# TK530_Kraftbakplan.net
KiCad netlist of a schematic drawn in Altium Designer
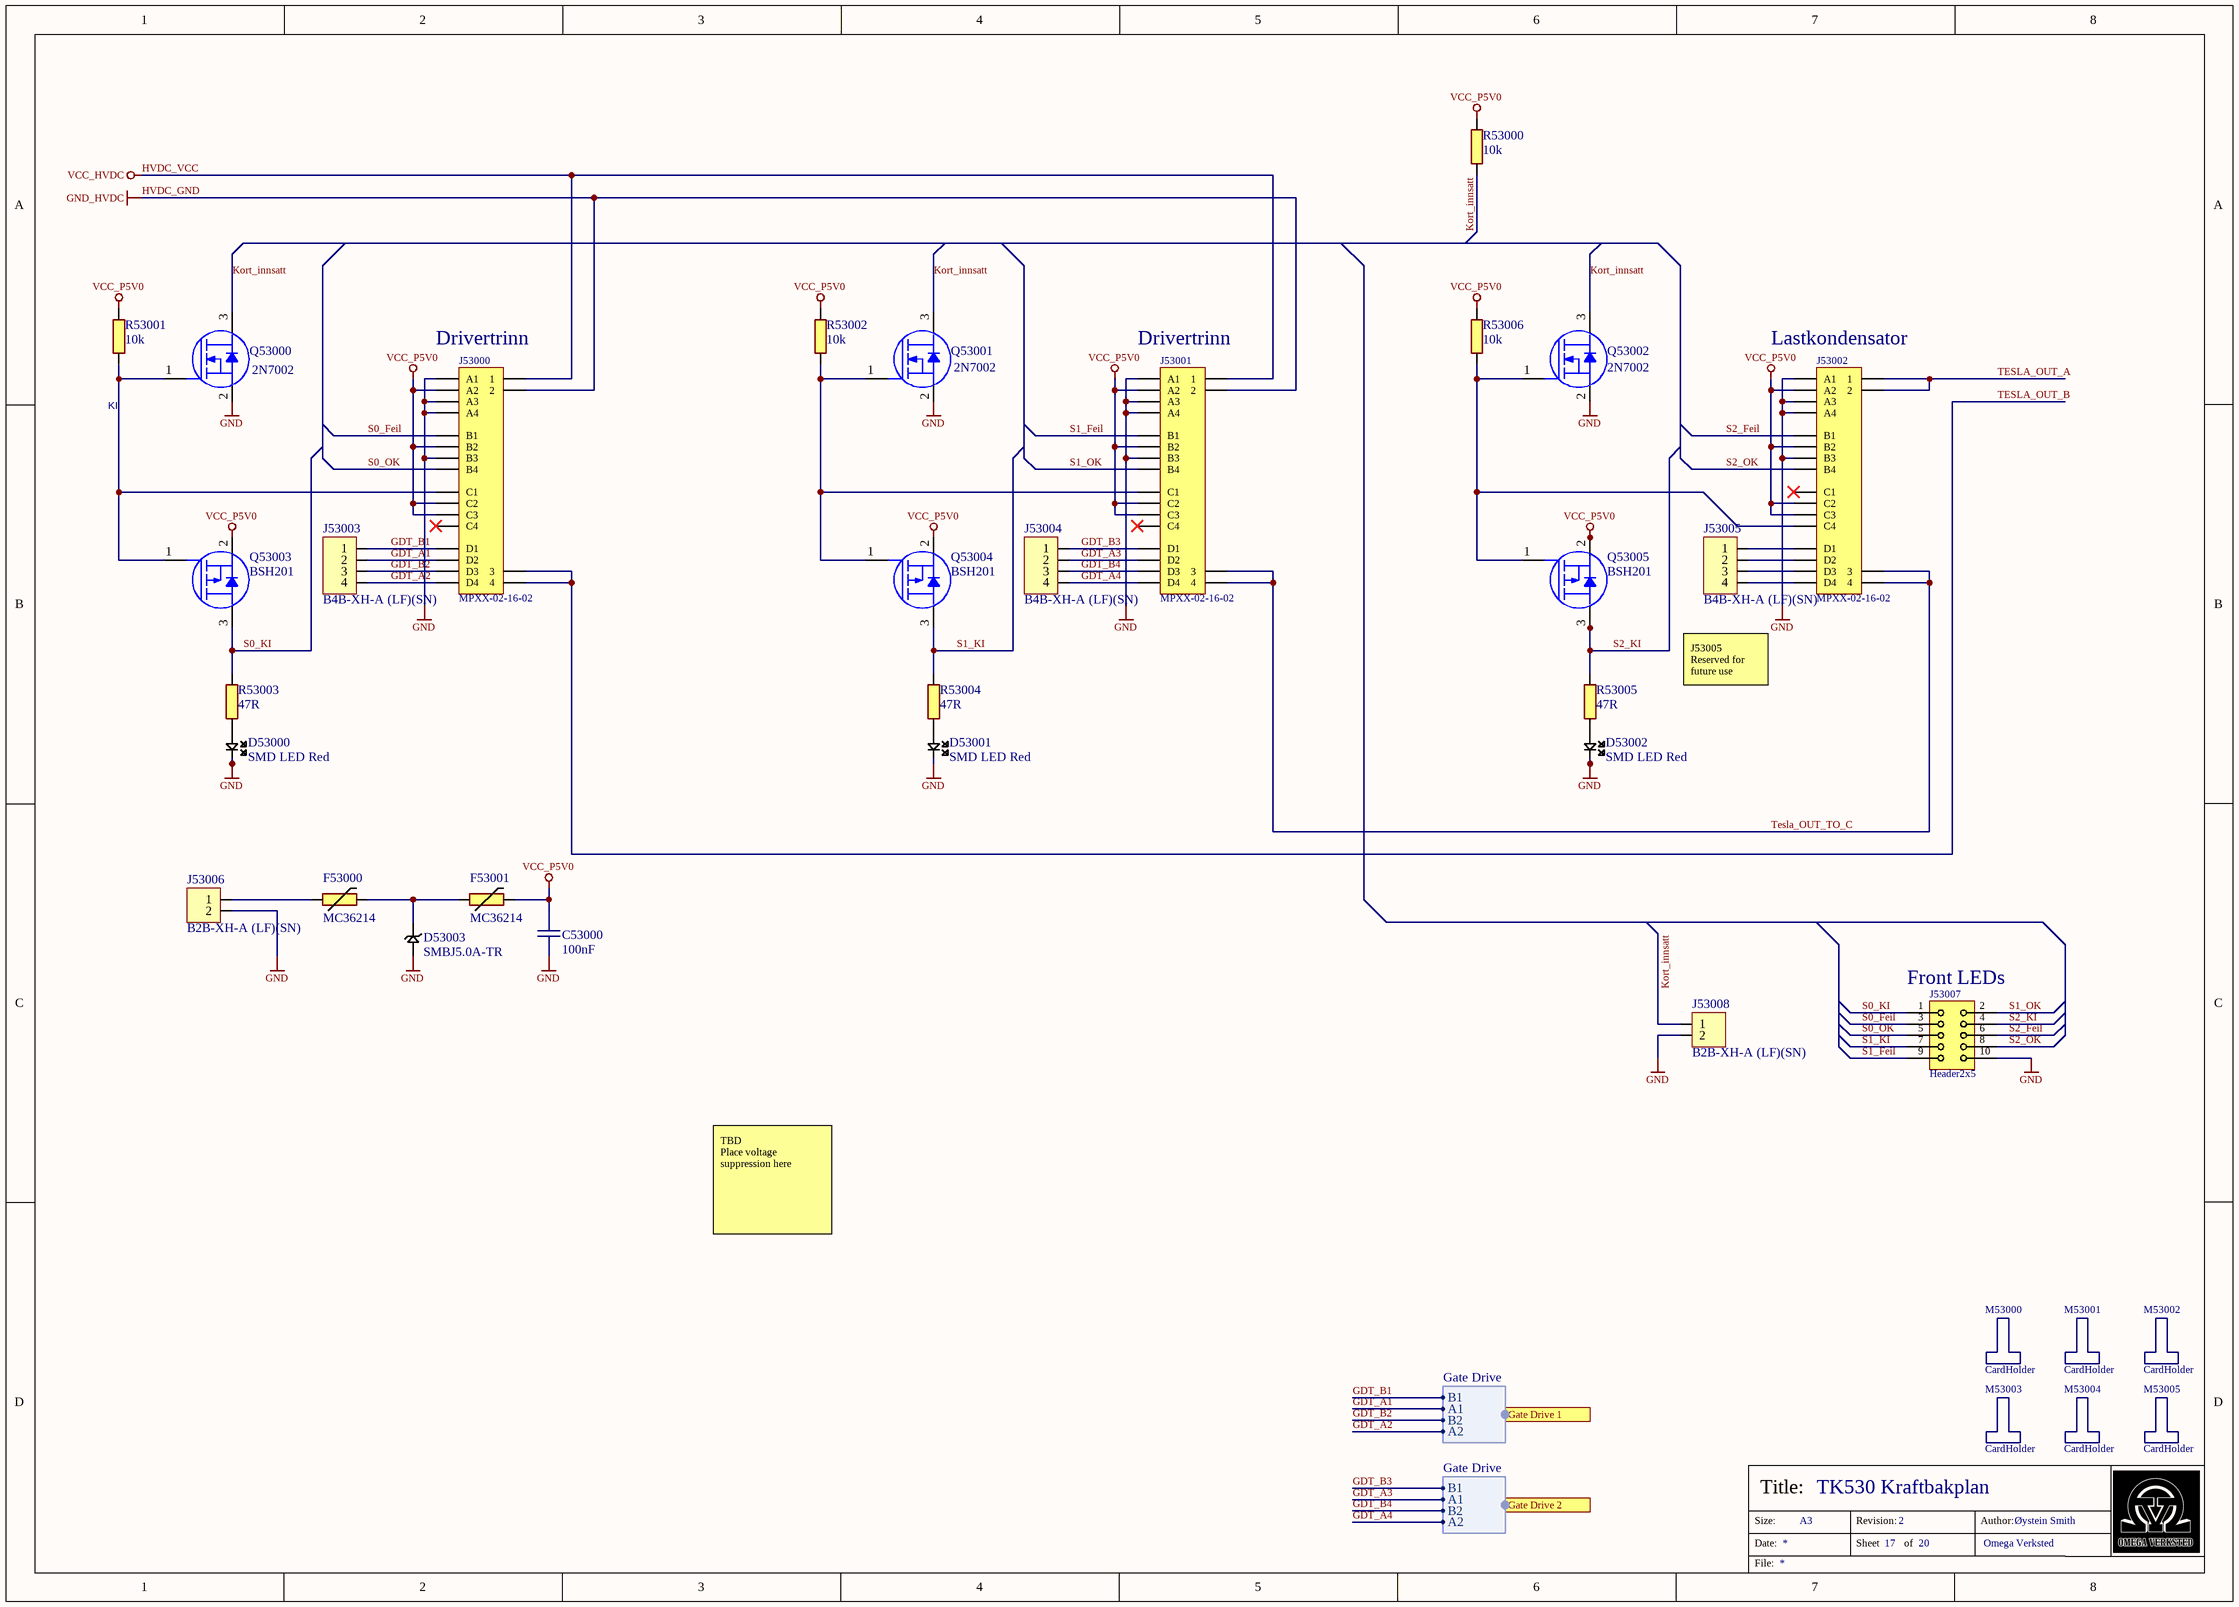
[diagram p0: TK530_Kraftbakplan.SchDoc]

(export (version "E")
  (design (tool "Eeschema 10.0.6"))
  (components
    (comp (ref "C53000")
      (value "100nF")
      (footprint "CAPC0603(1608)55_N")
      (description "X7R 50V 5%")
      (libsource (lib "OVLib_64") (part "CAP"))
    )
    (comp (ref "D53000")
      (value "SMD LED Red")
      (footprint "I_LEDC0603(1608)_N")
      (description "SMD")
      (libsource (lib "OVLib_64") (part "LED"))
    )
    (comp (ref "D53001")
      (value "SMD LED Red")
      (footprint "I_LEDC0603(1608)_N")
      (description "SMD")
      (libsource (lib "OVLib_64") (part "LED"))
    )
    (comp (ref "D53002")
      (value "SMD LED Red")
      (footprint "I_LEDC0603(1608)_N")
      (description "SMD")
      (libsource (lib "OVLib_64") (part "LED"))
    )
    (comp (ref "D53003")
      (value "SMBJ5.0A-TR")
      (footprint "SODFL535X245-2N")
      (description "Transient Voltage Suppressor, TVS, Transil SMBJ Series, Unidirectional, 5 V, SMD, 2, 6.4 V")
      (libsource (lib "OVLib_64") (part "TVSDiode"))
    )
    (comp (ref "F53000")
      (value "MC36214")
      (footprint "RESC0805(2012)_N")
      (description "FUSE, PTC RESET, SMD, 16V, 500MA")
      (libsource (lib "OVLib_64") (part "PTC"))
    )
    (comp (ref "F53001")
      (value "MC36214")
      (footprint "RESC0805(2012)_N")
      (description "FUSE, PTC RESET, SMD, 16V, 500MA")
      (libsource (lib "OVLib_64") (part "PTC"))
    )
    (comp (ref "J53000")
      (value "MPXX-02-16-02")
      (footprint "MPSC-02-16-02-7.70-03-L-V-LC")
      (description "SAMTEC Connector")
      (libsource (lib "OVLib_64") (part "MPXX-02-16-02"))
    )
    (comp (ref "J53001")
      (value "MPXX-02-16-02")
      (footprint "MPSC-02-16-02-7.70-03-L-V-LC")
      (description "SAMTEC Connector")
      (libsource (lib "OVLib_64") (part "MPXX-02-16-02"))
    )
    (comp (ref "J53002")
      (value "MPXX-02-16-02")
      (footprint "MPSC-02-16-02-7.70-03-L-V-LC")
      (description "SAMTEC Connector")
      (libsource (lib "OVLib_64") (part "MPXX-02-16-02"))
    )
    (comp (ref "J53003")
      (value "B4B-XH-A (LF)(SN)")
      (footprint "JST_4P")
      (description "JST 4pin (pris pr. stk.)")
      (libsource (lib "OVLib_64") (part "4PConnector"))
    )
    (comp (ref "J53004")
      (value "B4B-XH-A (LF)(SN)")
      (footprint "JST_4P")
      (description "JST 4pin (pris pr. stk.)")
      (libsource (lib "OVLib_64") (part "4PConnector"))
    )
    (comp (ref "J53005")
      (value "B4B-XH-A (LF)(SN)")
      (footprint "JST_4P")
      (description "JST 4pin (pris pr. stk.)")
      (libsource (lib "OVLib_64") (part "4PConnector"))
    )
    (comp (ref "J53006")
      (value "B2B-XH-A (LF)(SN)")
      (footprint "JST_2P")
      (description "JST 2pin (pris pr. stk.)")
      (libsource (lib "OVLib_64") (part "2PConnector"))
    )
    (comp (ref "J53007")
      (value "Header2x5")
      (footprint "HDRV10W64P254_2X5_2030X900X900B")
      (description "Header")
      (libsource (lib "OVLib_64") (part "Header2x5"))
    )
    (comp (ref "J53008")
      (value "B2B-XH-A (LF)(SN)")
      (footprint "JST_2P")
      (description "JST 2pin (pris pr. stk.)")
      (libsource (lib "") (part "2PConnector_1"))
    )
    (comp (ref "M53000")
      (value "CardHolder")
      (footprint "CardHolder900X1900X5000")
      (description "Støtter kort i bakplan")
      (libsource (lib "OVLib_64") (part "CardHolder"))
    )
    (comp (ref "M53001")
      (value "CardHolder")
      (footprint "CardHolder900X1900X5000")
      (description "Støtter kort i bakplan")
      (libsource (lib "OVLib_64") (part "CardHolder"))
    )
    (comp (ref "M53002")
      (value "CardHolder")
      (footprint "CardHolder900X1900X5000")
      (description "Støtter kort i bakplan")
      (libsource (lib "OVLib_64") (part "CardHolder"))
    )
    (comp (ref "M53003")
      (value "CardHolder")
      (footprint "CardHolder900X1900X5000")
      (description "Støtter kort i bakplan")
      (libsource (lib "OVLib_64") (part "CardHolder"))
    )
    (comp (ref "M53004")
      (value "CardHolder")
      (footprint "CardHolder900X1900X5000")
      (description "Støtter kort i bakplan")
      (libsource (lib "OVLib_64") (part "CardHolder"))
    )
    (comp (ref "M53005")
      (value "CardHolder")
      (footprint "CardHolder900X1900X5000")
      (description "Støtter kort i bakplan")
      (libsource (lib "OVLib_64") (part "CardHolder"))
    )
    (comp (ref "Q53000")
      (value "2N7002")
      (footprint "SOT323_N")
      (description "N-Channel MOSFET 300mA")
      (libsource (lib "OVLib_64") (part "MOSFET_N_GSD"))
    )
    (comp (ref "Q53001")
      (value "2N7002")
      (footprint "SOT323_N")
      (description "N-Channel MOSFET 300mA")
      (libsource (lib "OVLib_64") (part "MOSFET_N_GSD"))
    )
    (comp (ref "Q53002")
      (value "2N7002")
      (footprint "SOT323_N")
      (description "N-Channel MOSFET 300mA")
      (libsource (lib "OVLib_64") (part "MOSFET_N_GSD"))
    )
    (comp (ref "Q53003")
      (value "BSH201")
      (footprint "SOT23-3_N")
      (description "P-Channel MOSFET 300mA")
      (libsource (lib "OVLib_64") (part "MOSFET_P_GSD"))
    )
    (comp (ref "Q53004")
      (value "BSH201")
      (footprint "SOT23-3_N")
      (description "P-Channel MOSFET 300mA")
      (libsource (lib "OVLib_64") (part "MOSFET_P_GSD"))
    )
    (comp (ref "Q53005")
      (value "BSH201")
      (footprint "SOT23-3_N")
      (description "P-Channel MOSFET 300mA")
      (libsource (lib "OVLib_64") (part "MOSFET_P_GSD"))
    )
    (comp (ref "R53000")
      (value "10k")
      (footprint "RESC0603(1608)_N")
      (description "0.1W 1% Thick film resistor")
      (libsource (lib "OVLib_64") (part "Resistor2"))
    )
    (comp (ref "R53001")
      (value "10k")
      (footprint "RESC0603(1608)_N")
      (description "0.1W 1% Thick film resistor")
      (libsource (lib "OVLib_64") (part "Resistor2"))
    )
    (comp (ref "R53002")
      (value "10k")
      (footprint "RESC0603(1608)_N")
      (description "0.1W 1% Thick film resistor")
      (libsource (lib "OVLib_64") (part "Resistor2"))
    )
    (comp (ref "R53003")
      (value "47R")
      (footprint "RESC0603(1608)_N")
      (description "0.1W 1% Thick film resistor")
      (libsource (lib "OVLib_64") (part "Resistor2"))
    )
    (comp (ref "R53004")
      (value "47R")
      (footprint "RESC0603(1608)_N")
      (description "0.1W 1% Thick film resistor")
      (libsource (lib "OVLib_64") (part "Resistor2"))
    )
    (comp (ref "R53005")
      (value "47R")
      (footprint "RESC0603(1608)_N")
      (description "0.1W 1% Thick film resistor")
      (libsource (lib "OVLib_64") (part "Resistor2"))
    )
    (comp (ref "R53006")
      (value "10k")
      (footprint "RESC0603(1608)_N")
      (description "0.1W 1% Thick film resistor")
      (libsource (lib "OVLib_64") (part "Resistor2"))
    )
  )
  (nets
    (net (code "3") (name "/GDT_A1") (class "Default")
      (node (ref "J53000") (pin "18") (pinfunction "D2_18") (pintype "passive"))
      (node (ref "J53003") (pin "2") (pinfunction "2_2") (pintype "passive"))
    )
    (net (code "4") (name "/GDT_A2") (class "Default")
      (node (ref "J53000") (pin "20") (pinfunction "D4_20") (pintype "passive"))
      (node (ref "J53003") (pin "4") (pinfunction "4_4") (pintype "passive"))
    )
    (net (code "5") (name "/GDT_A3") (class "Default")
      (node (ref "J53001") (pin "18") (pinfunction "D2_18") (pintype "passive"))
      (node (ref "J53004") (pin "2") (pinfunction "2_2") (pintype "passive"))
    )
    (net (code "6") (name "/GDT_A4") (class "Default")
      (node (ref "J53001") (pin "20") (pinfunction "D4_20") (pintype "passive"))
      (node (ref "J53004") (pin "4") (pinfunction "4_4") (pintype "passive"))
    )
    (net (code "7") (name "/GDT_B1") (class "Default")
      (node (ref "J53000") (pin "17") (pinfunction "D1_17") (pintype "passive"))
      (node (ref "J53003") (pin "1") (pinfunction "1_1") (pintype "passive"))
    )
    (net (code "8") (name "/GDT_B2") (class "Default")
      (node (ref "J53000") (pin "19") (pinfunction "D3_19") (pintype "passive"))
      (node (ref "J53003") (pin "3") (pinfunction "3_3") (pintype "passive"))
    )
    (net (code "9") (name "/GDT_B3") (class "Default")
      (node (ref "J53001") (pin "17") (pinfunction "D1_17") (pintype "passive"))
      (node (ref "J53004") (pin "1") (pinfunction "1_1") (pintype "passive"))
    )
    (net (code "10") (name "/GDT_B4") (class "Default")
      (node (ref "J53001") (pin "19") (pinfunction "D3_19") (pintype "passive"))
      (node (ref "J53004") (pin "3") (pinfunction "3_3") (pintype "passive"))
    )
    (net (code "11") (name "/Kort_innsatt") (class "Default")
      (node (ref "J53008") (pin "1") (pinfunction "1_1") (pintype "passive"))
      (node (ref "Q53000") (pin "3") (pinfunction "Drain_3") (pintype "passive"))
      (node (ref "Q53001") (pin "3") (pinfunction "Drain_3") (pintype "passive"))
      (node (ref "Q53002") (pin "3") (pinfunction "Drain_3") (pintype "passive"))
      (node (ref "R53000") (pin "1") (pinfunction "1_1") (pintype "passive"))
    )
    (net (code "12") (name "/S0_Feil") (class "Default")
      (node (ref "J53000") (pin "9") (pinfunction "B1_9") (pintype "passive"))
      (node (ref "J53007") (pin "3") (pinfunction "3_3") (pintype "passive"))
    )
    (net (code "13") (name "/S0_KI") (class "Default")
      (node (ref "J53007") (pin "1") (pinfunction "1_1") (pintype "passive"))
      (node (ref "Q53003") (pin "3") (pinfunction "Drain_3") (pintype "passive"))
      (node (ref "R53003") (pin "2") (pinfunction "2_2") (pintype "passive"))
    )
    (net (code "14") (name "/S0_OK") (class "Default")
      (node (ref "J53000") (pin "12") (pinfunction "B4_12") (pintype "passive"))
      (node (ref "J53007") (pin "5") (pinfunction "5_5") (pintype "passive"))
    )
    (net (code "15") (name "/S1_Feil") (class "Default")
      (node (ref "J53001") (pin "9") (pinfunction "B1_9") (pintype "passive"))
      (node (ref "J53007") (pin "9") (pinfunction "9_9") (pintype "passive"))
    )
    (net (code "16") (name "/S1_KI") (class "Default")
      (node (ref "J53007") (pin "7") (pinfunction "7_7") (pintype "passive"))
      (node (ref "Q53004") (pin "3") (pinfunction "Drain_3") (pintype "passive"))
      (node (ref "R53004") (pin "2") (pinfunction "2_2") (pintype "passive"))
    )
    (net (code "17") (name "/S1_OK") (class "Default")
      (node (ref "J53001") (pin "12") (pinfunction "B4_12") (pintype "passive"))
      (node (ref "J53007") (pin "2") (pinfunction "2_2") (pintype "passive"))
    )
    (net (code "18") (name "/S2_Feil") (class "Default")
      (node (ref "J53002") (pin "9") (pinfunction "B1_9") (pintype "passive"))
      (node (ref "J53007") (pin "6") (pinfunction "6_6") (pintype "passive"))
    )
    (net (code "19") (name "/S2_KI") (class "Default")
      (node (ref "J53007") (pin "4") (pinfunction "4_4") (pintype "passive"))
      (node (ref "Q53005") (pin "3") (pinfunction "Drain_3") (pintype "passive"))
      (node (ref "R53005") (pin "2") (pinfunction "2_2") (pintype "passive"))
    )
    (net (code "20") (name "/S2_OK") (class "Default")
      (node (ref "J53002") (pin "12") (pinfunction "B4_12") (pintype "passive"))
      (node (ref "J53007") (pin "8") (pinfunction "8_8") (pintype "passive"))
    )
    (net (code "21") (name "/TESLA_OUT_A") (class "Default")
      (node (ref "J53002") (pin "1") (pinfunction "1_1") (pintype "passive"))
      (node (ref "J53002") (pin "2") (pinfunction "2_2") (pintype "passive"))
    )
    (net (code "22") (name "/TESLA_OUT_B") (class "Default")
      (node (ref "J53000") (pin "3") (pinfunction "3_3") (pintype "passive"))
      (node (ref "J53000") (pin "4") (pinfunction "4_4") (pintype "passive"))
    )
    (net (code "23") (name "/Tesla_OUT_TO_C") (class "Default")
      (node (ref "J53001") (pin "3") (pinfunction "3_3") (pintype "passive"))
      (node (ref "J53001") (pin "4") (pinfunction "4_4") (pintype "passive"))
      (node (ref "J53002") (pin "3") (pinfunction "3_3") (pintype "passive"))
      (node (ref "J53002") (pin "4") (pinfunction "4_4") (pintype "passive"))
    )
    (net (code "25") (name "GND") (class "Default")
      (node (ref "C53000") (pin "1") (pinfunction "1_1") (pintype "passive"))
      (node (ref "D53000") (pin "2") (pinfunction "2_2") (pintype "passive"))
      (node (ref "D53001") (pin "2") (pinfunction "2_2") (pintype "passive"))
      (node (ref "D53002") (pin "2") (pinfunction "2_2") (pintype "passive"))
      (node (ref "D53003") (pin "1") (pinfunction "A_1") (pintype "passive"))
      (node (ref "J53000") (pin "11") (pinfunction "B3_11") (pintype "passive"))
      (node (ref "J53000") (pin "5") (pinfunction "A1_5") (pintype "passive"))
      (node (ref "J53000") (pin "7") (pinfunction "A3_7") (pintype "passive"))
      (node (ref "J53000") (pin "8") (pinfunction "A4_8") (pintype "passive"))
      (node (ref "J53001") (pin "11") (pinfunction "B3_11") (pintype "passive"))
      (node (ref "J53001") (pin "5") (pinfunction "A1_5") (pintype "passive"))
      (node (ref "J53001") (pin "7") (pinfunction "A3_7") (pintype "passive"))
      (node (ref "J53001") (pin "8") (pinfunction "A4_8") (pintype "passive"))
      (node (ref "J53002") (pin "11") (pinfunction "B3_11") (pintype "passive"))
      (node (ref "J53002") (pin "5") (pinfunction "A1_5") (pintype "passive"))
      (node (ref "J53002") (pin "7") (pinfunction "A3_7") (pintype "passive"))
      (node (ref "J53002") (pin "8") (pinfunction "A4_8") (pintype "passive"))
      (node (ref "J53006") (pin "2") (pinfunction "2_2") (pintype "passive"))
      (node (ref "J53007") (pin "10") (pinfunction "10_10") (pintype "passive"))
      (node (ref "J53008") (pin "2") (pinfunction "2_2") (pintype "passive"))
      (node (ref "Q53000") (pin "2") (pinfunction "Source_2") (pintype "passive"))
      (node (ref "Q53001") (pin "2") (pinfunction "Source_2") (pintype "passive"))
      (node (ref "Q53002") (pin "2") (pinfunction "Source_2") (pintype "passive"))
    )
    (net (code "26") (name "GND_HVDC") (class "Default")
      (node (ref "J53000") (pin "2") (pinfunction "2_2") (pintype "passive"))
      (node (ref "J53001") (pin "2") (pinfunction "2_2") (pintype "passive"))
    )
    (net (code "27") (name "Net-(D53000-Pad1)") (class "Default")
      (node (ref "D53000") (pin "1") (pinfunction "1_1") (pintype "passive"))
      (node (ref "R53003") (pin "1") (pinfunction "1_1") (pintype "passive"))
    )
    (net (code "28") (name "Net-(D53001-Pad1)") (class "Default")
      (node (ref "D53001") (pin "1") (pinfunction "1_1") (pintype "passive"))
      (node (ref "R53004") (pin "1") (pinfunction "1_1") (pintype "passive"))
    )
    (net (code "29") (name "Net-(D53002-Pad1)") (class "Default")
      (node (ref "D53002") (pin "1") (pinfunction "1_1") (pintype "passive"))
      (node (ref "R53005") (pin "1") (pinfunction "1_1") (pintype "passive"))
    )
    (net (code "30") (name "Net-(D53003-K)") (class "Default")
      (node (ref "D53003") (pin "2") (pinfunction "K_2") (pintype "passive"))
      (node (ref "F53000") (pin "2") (pinfunction "2_2") (pintype "passive"))
      (node (ref "F53001") (pin "1") (pinfunction "1_1") (pintype "passive"))
    )
    (net (code "31") (name "Net-(F53000-Pad1)") (class "Default")
      (node (ref "F53000") (pin "1") (pinfunction "1_1") (pintype "passive"))
      (node (ref "J53006") (pin "1") (pinfunction "1_1") (pintype "passive"))
    )
    (net (code "32") (name "Net-(J53000-C1)") (class "Default")
      (node (ref "J53000") (pin "13") (pinfunction "C1_13") (pintype "passive"))
      (node (ref "Q53000") (pin "1") (pinfunction "Gate_1") (pintype "passive"))
      (node (ref "Q53003") (pin "1") (pinfunction "Gate_1") (pintype "passive"))
      (node (ref "R53001") (pin "1") (pinfunction "1_1") (pintype "passive"))
    )
    (net (code "33") (name "Net-(J53001-C1)") (class "Default")
      (node (ref "J53001") (pin "13") (pinfunction "C1_13") (pintype "passive"))
      (node (ref "Q53001") (pin "1") (pinfunction "Gate_1") (pintype "passive"))
      (node (ref "Q53004") (pin "1") (pinfunction "Gate_1") (pintype "passive"))
      (node (ref "R53002") (pin "1") (pinfunction "1_1") (pintype "passive"))
    )
    (net (code "34") (name "Net-(J53002-C4)") (class "Default")
      (node (ref "J53002") (pin "16") (pinfunction "C4_16") (pintype "passive"))
      (node (ref "Q53002") (pin "1") (pinfunction "Gate_1") (pintype "passive"))
      (node (ref "Q53005") (pin "1") (pinfunction "Gate_1") (pintype "passive"))
      (node (ref "R53006") (pin "1") (pinfunction "1_1") (pintype "passive"))
    )
    (net (code "35") (name "Net-(J53002-D1)") (class "Default")
      (node (ref "J53002") (pin "17") (pinfunction "D1_17") (pintype "passive"))
      (node (ref "J53005") (pin "1") (pinfunction "1_1") (pintype "passive"))
    )
    (net (code "36") (name "Net-(J53002-D2)") (class "Default")
      (node (ref "J53002") (pin "18") (pinfunction "D2_18") (pintype "passive"))
      (node (ref "J53005") (pin "2") (pinfunction "2_2") (pintype "passive"))
    )
    (net (code "37") (name "Net-(J53002-D3)") (class "Default")
      (node (ref "J53002") (pin "19") (pinfunction "D3_19") (pintype "passive"))
      (node (ref "J53005") (pin "3") (pinfunction "3_3") (pintype "passive"))
    )
    (net (code "38") (name "Net-(J53002-D4)") (class "Default")
      (node (ref "J53002") (pin "20") (pinfunction "D4_20") (pintype "passive"))
      (node (ref "J53005") (pin "4") (pinfunction "4_4") (pintype "passive"))
    )
    (net (code "39") (name "VCC_HVDC") (class "Default")
      (node (ref "J53000") (pin "1") (pinfunction "1_1") (pintype "passive"))
      (node (ref "J53001") (pin "1") (pinfunction "1_1") (pintype "passive"))
    )
    (net (code "40") (name "VCC_P5V0") (class "Default")
      (node (ref "C53000") (pin "2") (pinfunction "2_2") (pintype "passive"))
      (node (ref "F53001") (pin "2") (pinfunction "2_2") (pintype "passive"))
      (node (ref "J53000") (pin "10") (pinfunction "B2_10") (pintype "passive"))
      (node (ref "J53000") (pin "14") (pinfunction "C2_14") (pintype "passive"))
      (node (ref "J53000") (pin "15") (pinfunction "C3_15") (pintype "passive"))
      (node (ref "J53000") (pin "6") (pinfunction "A2_6") (pintype "passive"))
      (node (ref "J53001") (pin "10") (pinfunction "B2_10") (pintype "passive"))
      (node (ref "J53001") (pin "14") (pinfunction "C2_14") (pintype "passive"))
      (node (ref "J53001") (pin "15") (pinfunction "C3_15") (pintype "passive"))
      (node (ref "J53001") (pin "6") (pinfunction "A2_6") (pintype "passive"))
      (node (ref "J53002") (pin "10") (pinfunction "B2_10") (pintype "passive"))
      (node (ref "J53002") (pin "14") (pinfunction "C2_14") (pintype "passive"))
      (node (ref "J53002") (pin "15") (pinfunction "C3_15") (pintype "passive"))
      (node (ref "J53002") (pin "6") (pinfunction "A2_6") (pintype "passive"))
      (node (ref "Q53003") (pin "2") (pinfunction "Source_2") (pintype "passive"))
      (node (ref "Q53004") (pin "2") (pinfunction "Source_2") (pintype "passive"))
      (node (ref "Q53005") (pin "2") (pinfunction "Source_2") (pintype "passive"))
      (node (ref "R53000") (pin "2") (pinfunction "2_2") (pintype "passive"))
      (node (ref "R53001") (pin "2") (pinfunction "2_2") (pintype "passive"))
      (node (ref "R53002") (pin "2") (pinfunction "2_2") (pintype "passive"))
      (node (ref "R53006") (pin "2") (pinfunction "2_2") (pintype "passive"))
    )
    (net (code "41") (name "unconnected-(J53000-C4-Pad16)") (class "Default")
      (node (ref "J53000") (pin "16") (pinfunction "C4_16") (pintype "passive+no_connect"))
    )
    (net (code "42") (name "unconnected-(J53001-C4-Pad16)") (class "Default")
      (node (ref "J53001") (pin "16") (pinfunction "C4_16") (pintype "passive+no_connect"))
    )
    (net (code "43") (name "unconnected-(J53002-C1-Pad13)") (class "Default")
      (node (ref "J53002") (pin "13") (pinfunction "C1_13") (pintype "passive+no_connect"))
    )
  )
)
